# Amplifier.net
KiCad netlist of a schematic drawn in Altium Designer
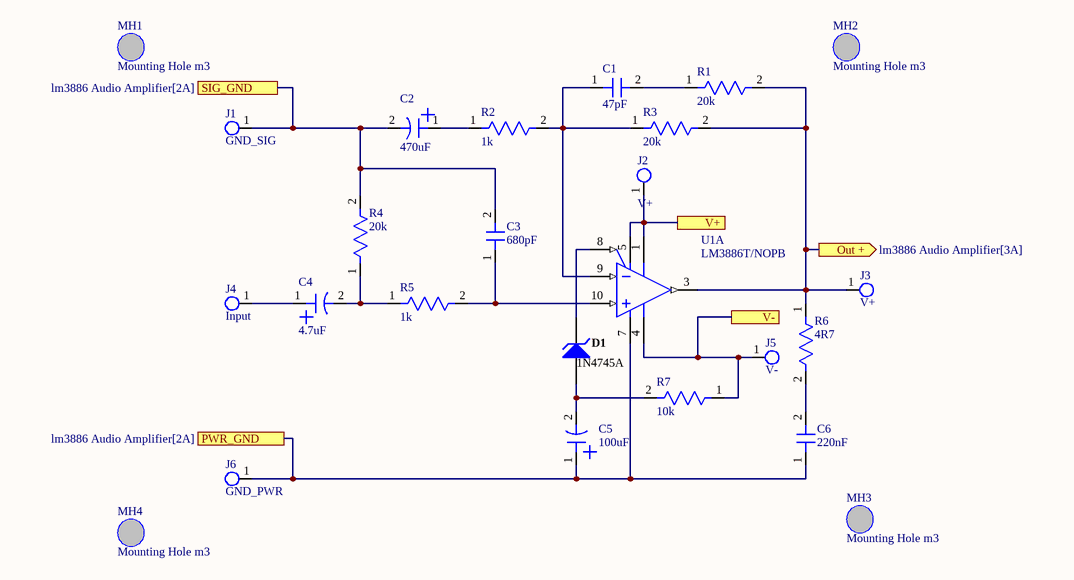
[diagram p0: Amplifier.SchDoc]

(export (version "E")
  (design (tool "Eeschema 10.0.6"))
  (components
    (comp (ref "C1")
      (value "47pF")
      (footprint "Capacitor P5 2.4x4.4mm")
      (libsource (lib "lm3886 Schlib") (part "Capacitor"))
    )
    (comp (ref "C2")
      (value "470uF")
      (footprint "Capacitor electrolytic 10x16mm")
      (libsource (lib "") (part "Capacitor Polar_1"))
    )
    (comp (ref "C3")
      (value "680pF")
      (footprint "Capacitor P5 2.4x4.4mm")
      (libsource (lib "lm3886 Schlib") (part "Capacitor"))
    )
    (comp (ref "C4")
      (value "4.7uF")
      (footprint "Capacitor electrolytic 5x11mm")
      (libsource (lib "") (part "Capacitor Polar_1"))
    )
    (comp (ref "C5")
      (value "100uF")
      (footprint "Capacitor electrolytic 6x11mm")
      (libsource (lib "lm3886 Schlib") (part "Capacitor Polar"))
    )
    (comp (ref "C6")
      (value "220nF")
      (footprint "Capacitor P5 5x7.5mm")
      (libsource (lib "lm3886 Schlib") (part "Capacitor"))
    )
    (comp (ref "D1")
      (value "1N4745A")
      (footprint "FAIR-DO-41-2_V")
      (description "Zener Diode, 16V, 1W, 5%, -65 to 200 degC, 2-Pin DO-41, Body 2.72 x 5.2 mm, RoHS")
      (fields (field (name "MANUFACTURER") "Fairchild Semiconductor") (field (name "TOLERANCE") "5%"))
      (libsource (lib "Altium Content Vault") (part "FAIR-DZEN-A1K2-2"))
    )
    (comp (ref "J1")
      (value "GND_SIG")
      (footprint "Terminal 6.3mm male")
      (libsource (lib "lm3886 Schlib") (part "6.3mm Male Terminal"))
    )
    (comp (ref "J2")
      (value "V+")
      (footprint "Terminal 6.3mm male")
      (libsource (lib "lm3886 Schlib") (part "6.3mm Male Terminal"))
    )
    (comp (ref "J3")
      (value "V+")
      (footprint "Terminal 6.3mm male")
      (libsource (lib "lm3886 Schlib") (part "6.3mm Male Terminal"))
    )
    (comp (ref "J4")
      (value "Input")
      (footprint "Terminal 6.3mm male")
      (libsource (lib "lm3886 Schlib") (part "6.3mm Male Terminal"))
    )
    (comp (ref "J5")
      (value "V-")
      (footprint "Terminal 6.3mm male")
      (libsource (lib "lm3886 Schlib") (part "6.3mm Male Terminal"))
    )
    (comp (ref "J6")
      (value "GND_PWR")
      (footprint "Terminal 6.3mm male")
      (libsource (lib "lm3886 Schlib") (part "6.3mm Male Terminal"))
    )
    (comp (ref "MH1")
      (value "Mounting Hole m3")
      (footprint "Mounting Hole")
      (libsource (lib "lm3886 Schlib") (part "Mounting Hole m3"))
    )
    (comp (ref "MH2")
      (value "Mounting Hole m3")
      (footprint "Mounting Hole")
      (libsource (lib "lm3886 Schlib") (part "Mounting Hole m3"))
    )
    (comp (ref "MH3")
      (value "Mounting Hole m3")
      (footprint "Mounting Hole")
      (libsource (lib "lm3886 Schlib") (part "Mounting Hole m3"))
    )
    (comp (ref "MH4")
      (value "Mounting Hole m3")
      (footprint "Mounting Hole")
      (libsource (lib "lm3886 Schlib") (part "Mounting Hole m3"))
    )
    (comp (ref "R1")
      (value "20k")
      (footprint "Resistor 0207 1/4W")
      (libsource (lib "lm3886 Schlib") (part "Resistor"))
    )
    (comp (ref "R2")
      (value "1k")
      (footprint "Resistor 0207 1/4W")
      (libsource (lib "lm3886 Schlib") (part "Resistor"))
    )
    (comp (ref "R3")
      (value "20k")
      (footprint "Resistor 0207 1/4W")
      (libsource (lib "lm3886 Schlib") (part "Resistor"))
    )
    (comp (ref "R4")
      (value "20k")
      (footprint "Resistor 0207 1/4W")
      (libsource (lib "lm3886 Schlib") (part "Resistor"))
    )
    (comp (ref "R5")
      (value "1k")
      (footprint "Resistor 0207 1/4W")
      (libsource (lib "lm3886 Schlib") (part "Resistor"))
    )
    (comp (ref "R6")
      (value "4R7")
      (footprint "Resistor 0617 2W")
      (libsource (lib "lm3886 Schlib") (part "Resistor"))
    )
    (comp (ref "R7")
      (value "10k")
      (footprint "Resistor 0207 1/4W")
      (libsource (lib "lm3886 Schlib") (part "Resistor"))
    )
    (comp (ref "U1")
      (value "LM3886T/NOPB")
      (footprint "TI-NDJ11")
      (fields (field (name "MANUFACTURER") "Texas Instruments"))
      (libsource (lib "Altium Content Vault") (part "TI-LM3886undefined"))
    )
  )
  (nets
    (net (code "1") (name "/Out +") (class "Default")
      (node (ref "J3") (pin "1") (pintype "passive"))
      (node (ref "R1") (pin "2") (pintype "passive"))
      (node (ref "R3") (pin "2") (pintype "passive"))
      (node (ref "R6") (pin "1") (pintype "passive"))
      (node (ref "U1") (pin "3") (pinfunction "OUTPUT_3") (pintype "output"))
    )
    (net (code "2") (name "/PWR_GND") (class "Default")
      (node (ref "C5") (pin "1") (pintype "passive"))
      (node (ref "C6") (pin "1") (pintype "passive"))
      (node (ref "J6") (pin "1") (pintype "passive"))
      (node (ref "U1") (pin "7") (pinfunction "GND_7") (pintype "power_in"))
    )
    (net (code "3") (name "/SIG_GND") (class "Default")
      (node (ref "C2") (pin "2") (pintype "passive"))
      (node (ref "C3") (pin "2") (pintype "passive"))
      (node (ref "J1") (pin "1") (pintype "passive"))
      (node (ref "R4") (pin "2") (pintype "passive"))
    )
    (net (code "4") (name "/V+") (class "Default")
      (node (ref "J2") (pin "1") (pintype "passive"))
      (node (ref "U1") (pin "1") (pinfunction "V+_1") (pintype "power_in"))
      (node (ref "U1") (pin "5") (pinfunction "V+_5") (pintype "power_in"))
    )
    (net (code "5") (name "/V-") (class "Default")
      (node (ref "J5") (pin "1") (pintype "passive"))
      (node (ref "R7") (pin "1") (pintype "passive"))
      (node (ref "U1") (pin "4") (pinfunction "V-_4") (pintype "power_in"))
    )
    (net (code "6") (name "Net-(C1-Pad2)") (class "Default")
      (node (ref "C1") (pin "2") (pintype "passive"))
      (node (ref "R1") (pin "1") (pintype "passive"))
    )
    (net (code "7") (name "Net-(C2-Pad1)") (class "Default")
      (node (ref "C2") (pin "1") (pintype "passive"))
      (node (ref "R2") (pin "1") (pintype "passive"))
    )
    (net (code "8") (name "Net-(C4-Pad1)") (class "Default")
      (node (ref "C4") (pin "1") (pintype "passive"))
      (node (ref "J4") (pin "1") (pintype "passive"))
    )
    (net (code "9") (name "Net-(C4-Pad2)") (class "Default")
      (node (ref "C4") (pin "2") (pintype "passive"))
      (node (ref "R4") (pin "1") (pintype "passive"))
      (node (ref "R5") (pin "1") (pintype "passive"))
    )
    (net (code "10") (name "Net-(C6-Pad2)") (class "Default")
      (node (ref "C6") (pin "2") (pintype "passive"))
      (node (ref "R6") (pin "2") (pintype "passive"))
    )
    (net (code "11") (name "Net-(D1-A)") (class "Default")
      (node (ref "C5") (pin "2") (pintype "passive"))
      (node (ref "D1") (pin "1") (pinfunction "A_1") (pintype "passive"))
      (node (ref "R7") (pin "2") (pintype "passive"))
    )
    (net (code "12") (name "Net-(D1-K)") (class "Default")
      (node (ref "D1") (pin "2") (pinfunction "K_2") (pintype "passive"))
      (node (ref "U1") (pin "8") (pinfunction "MUTE_8") (pintype "input"))
    )
    (net (code "13") (name "Net-(U1A-VIN+)") (class "Default")
      (node (ref "C3") (pin "1") (pintype "passive"))
      (node (ref "R5") (pin "2") (pintype "passive"))
      (node (ref "U1") (pin "10") (pinfunction "VIN+_10") (pintype "input"))
    )
    (net (code "14") (name "Net-(U1A-VIN-)") (class "Default")
      (node (ref "C1") (pin "1") (pintype "passive"))
      (node (ref "R2") (pin "2") (pintype "passive"))
      (node (ref "R3") (pin "1") (pintype "passive"))
      (node (ref "U1") (pin "9") (pinfunction "VIN-_9") (pintype "input"))
    )
  )
)
